# MM2_plates.net
KiCad netlist of a schematic drawn in EAGLE
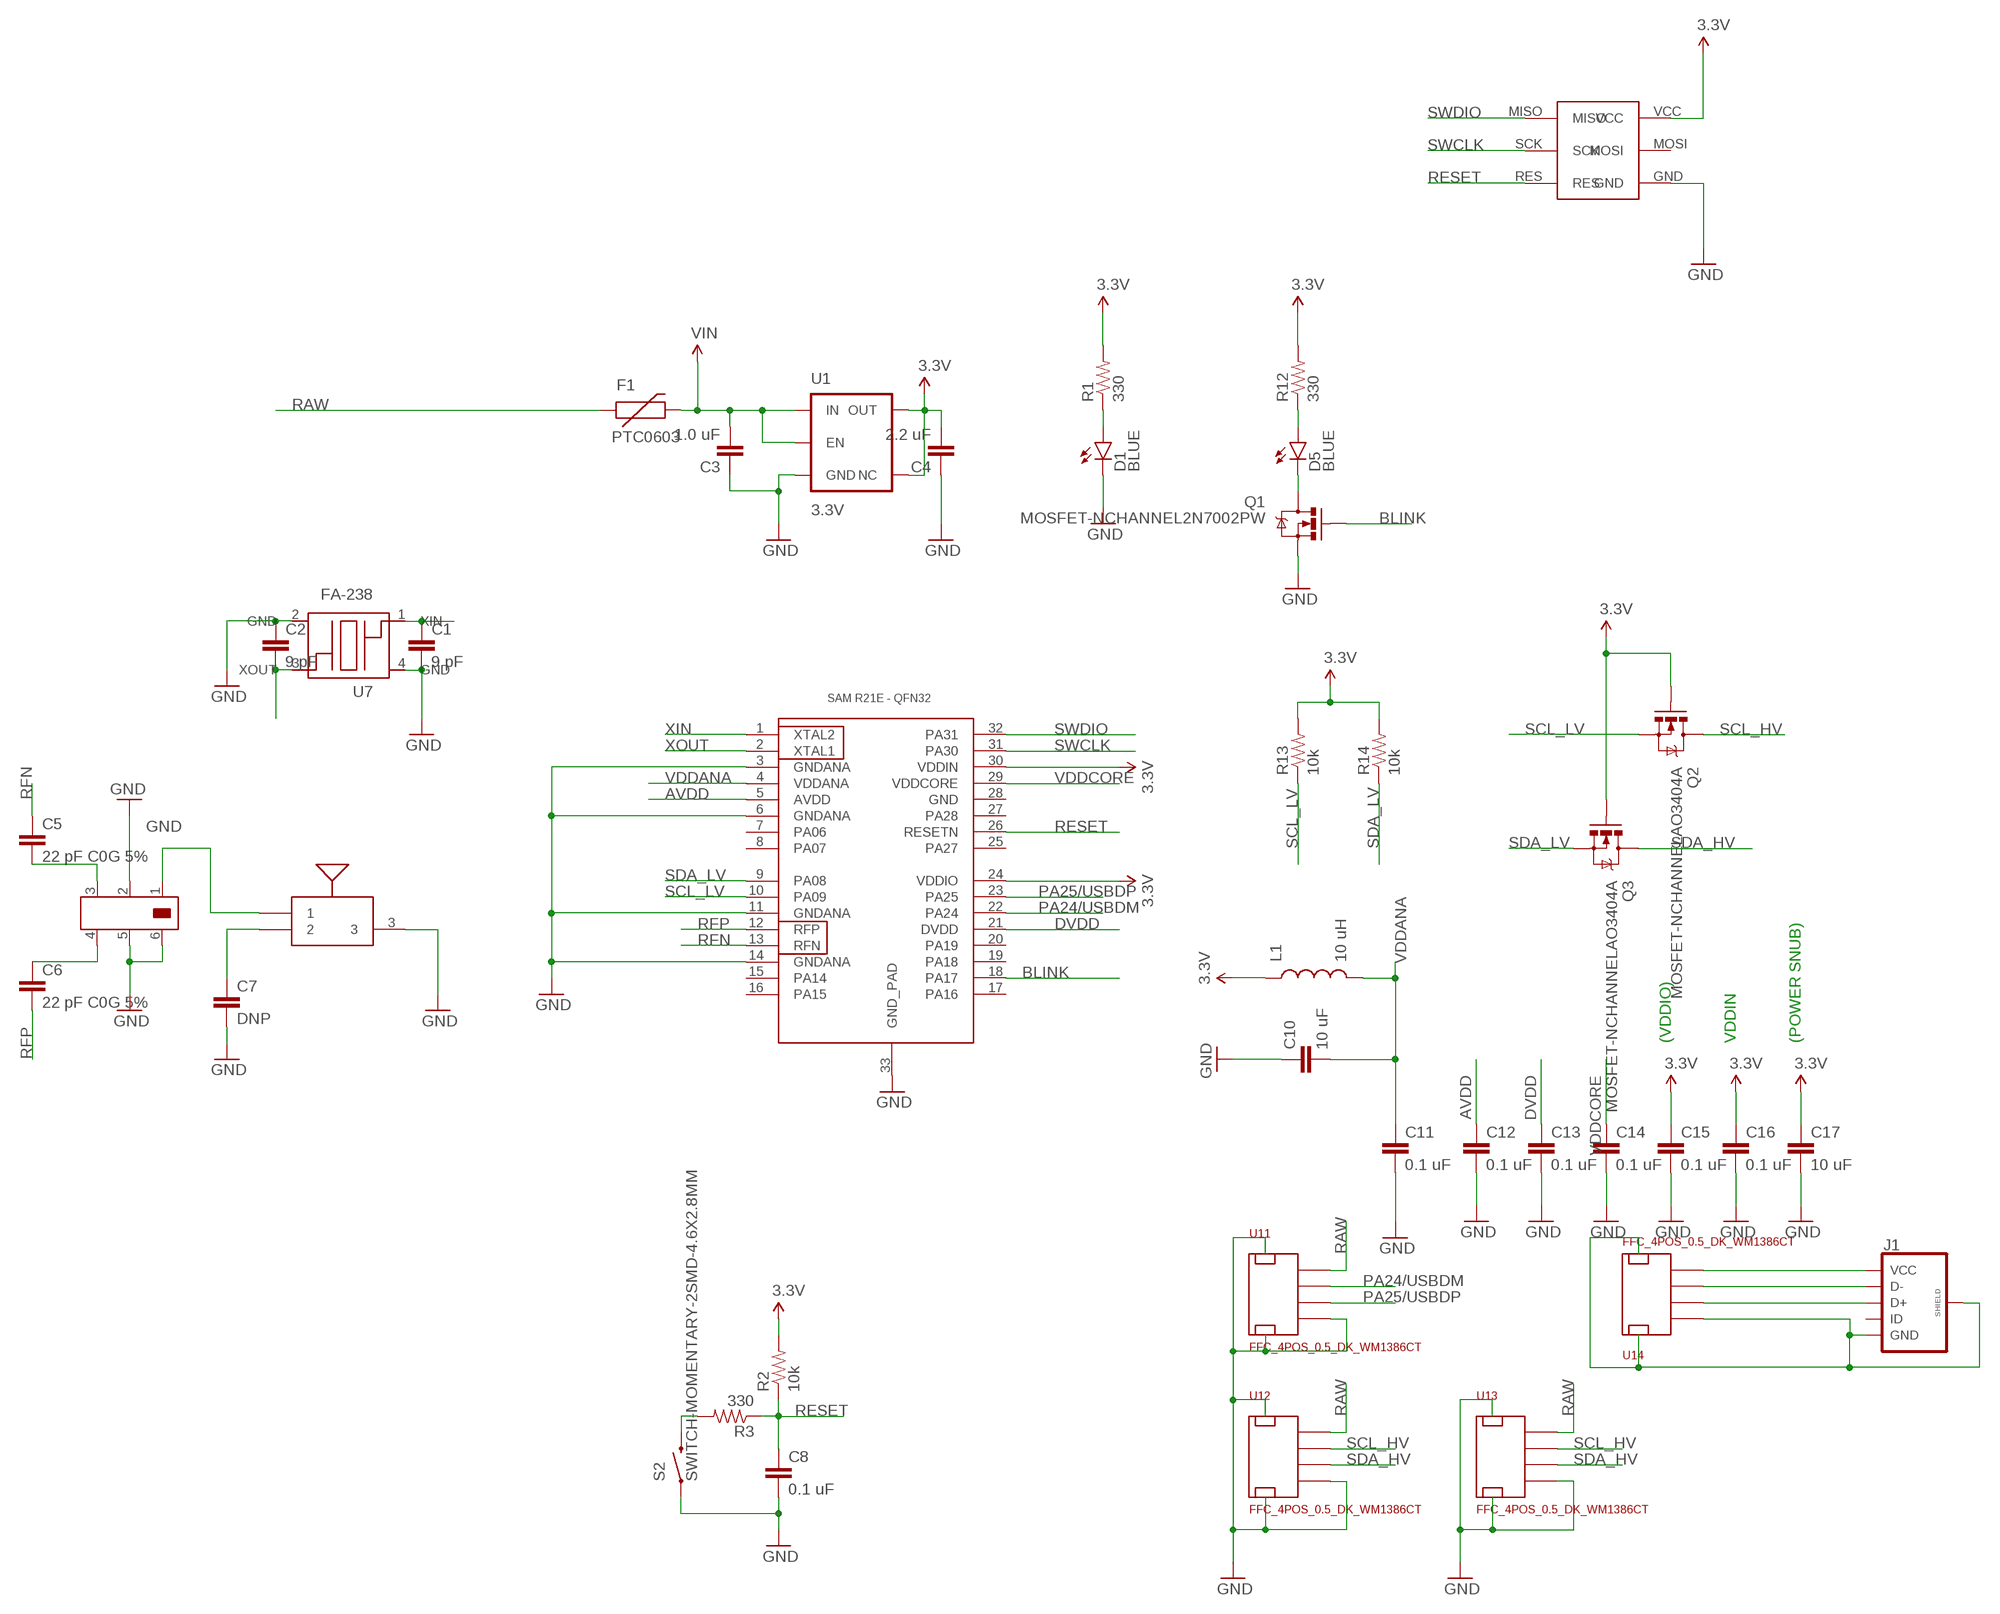
[diagram p0: schematic, sheet 1, part 1 of 2]
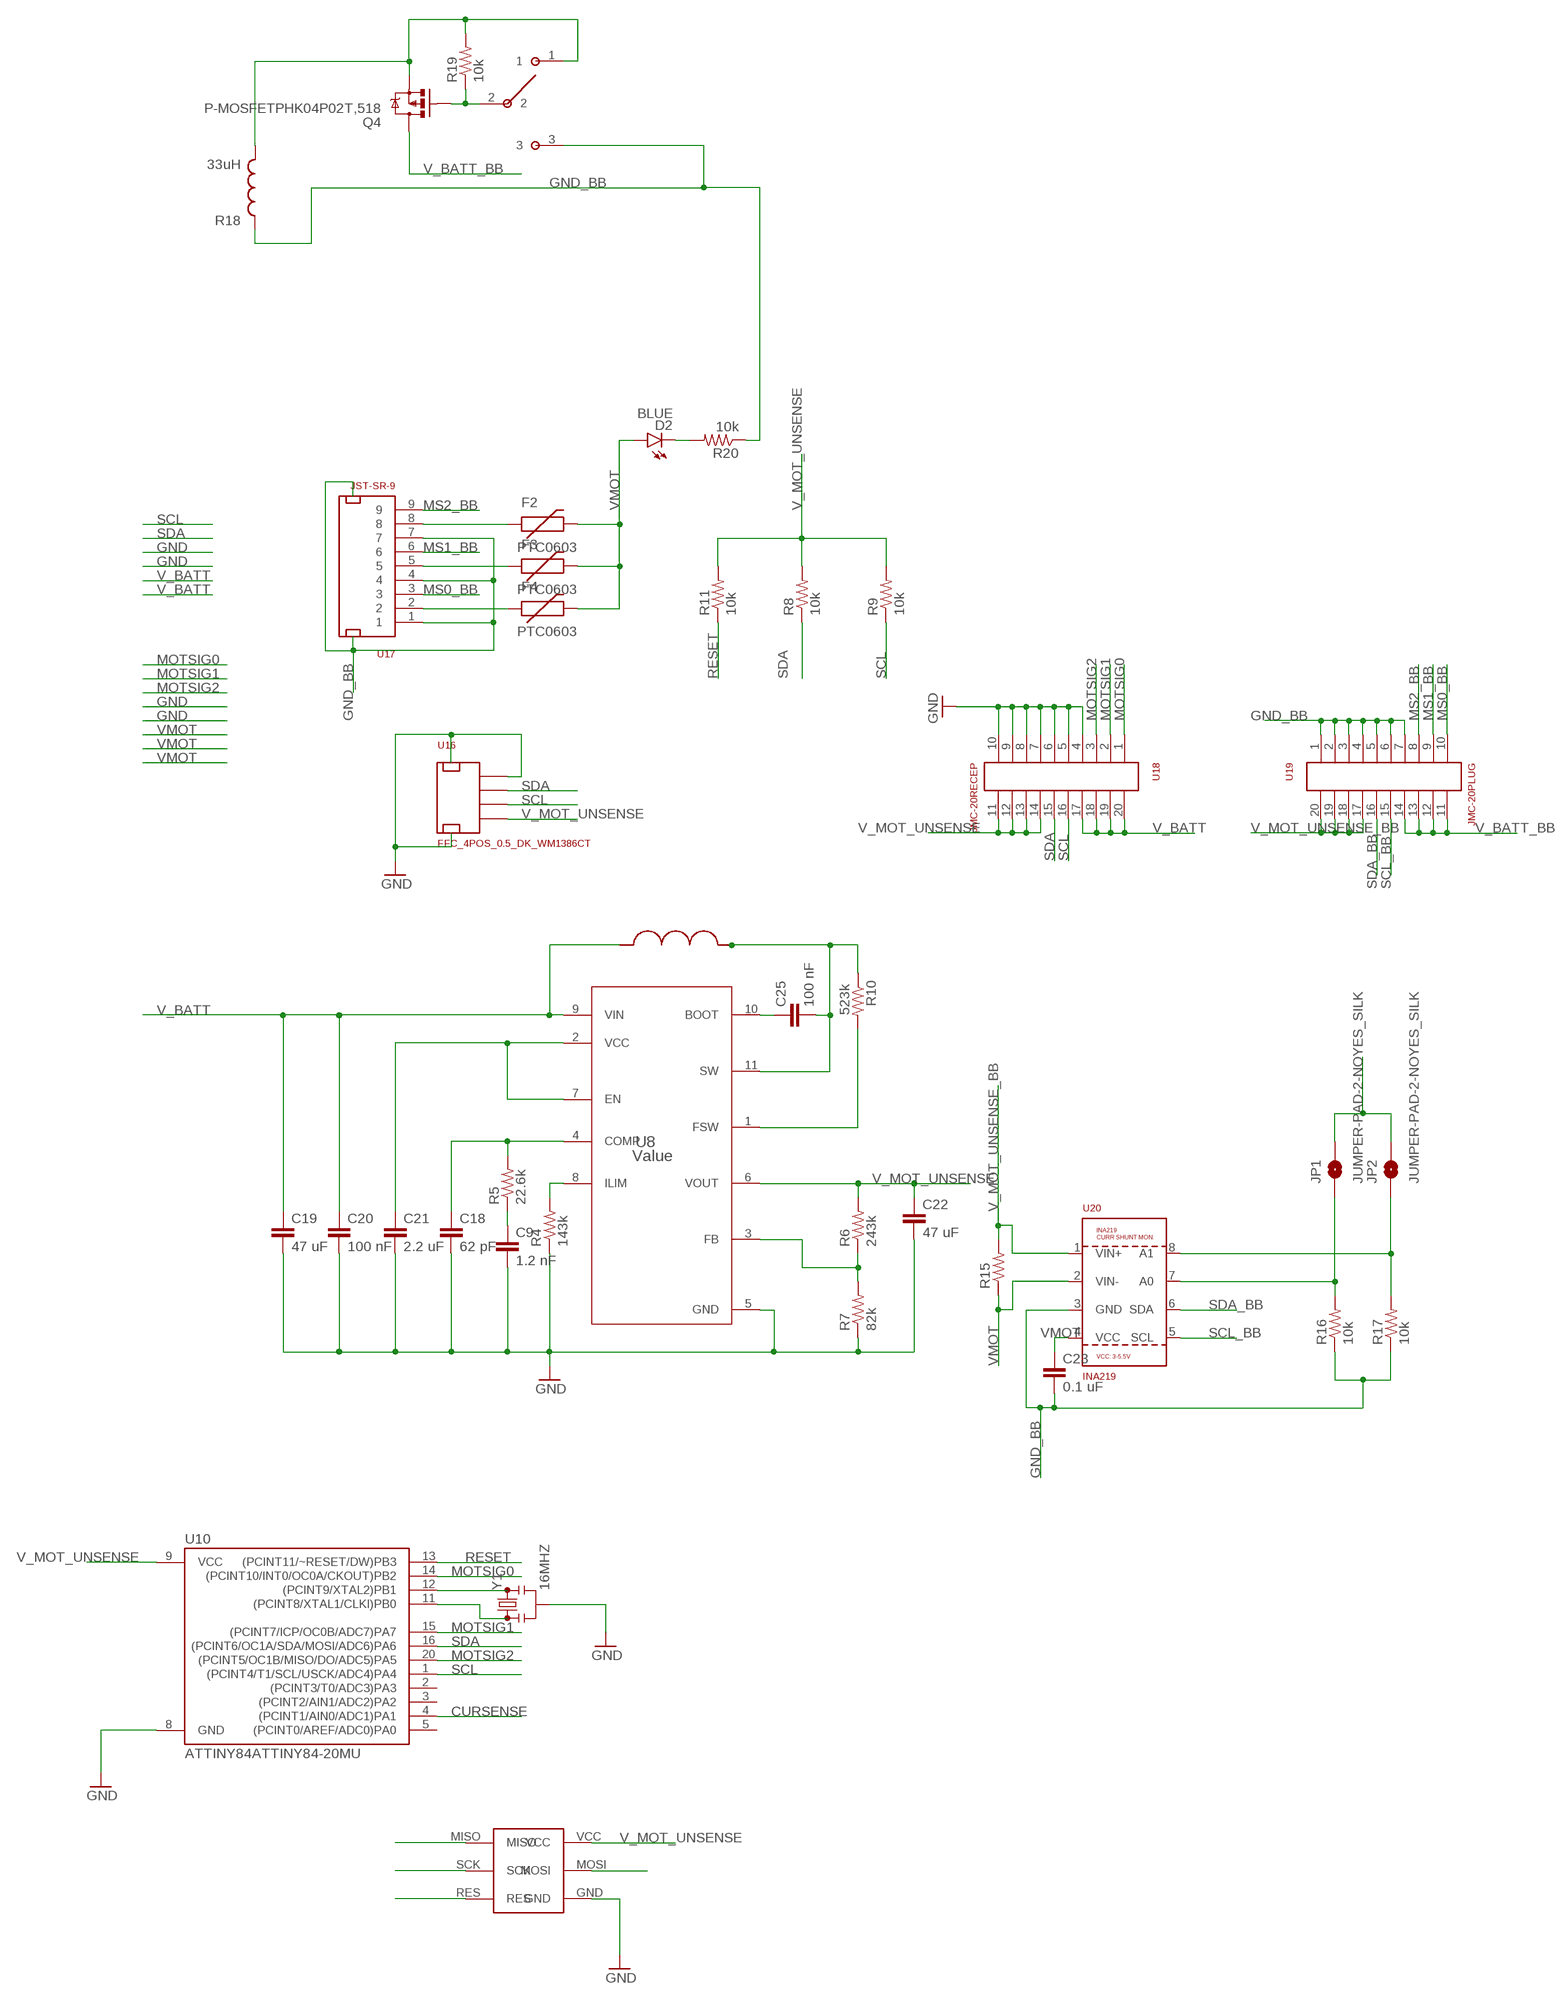
[diagram p1: schematic, sheet 1, part 2 of 2]

(export (version "E")
  (design (tool "Eeschema 10.0.6"))
  (components
    (comp (ref "C1")
      (value "9 pF")
      (footprint "eagle-import:0402-CAP")
      (libsource (lib "eagle-import") (part "CAP0402-CAP"))
    )
    (comp (ref "C2")
      (value "9 pF")
      (footprint "eagle-import:0402-CAP")
      (libsource (lib "eagle-import") (part "CAP0402-CAP"))
    )
    (comp (ref "C3")
      (value "1.0 uF")
      (footprint "eagle-import:0402-CAP")
      (libsource (lib "eagle-import") (part "CAP0402-CAP"))
    )
    (comp (ref "C4")
      (value "2.2 uF")
      (footprint "eagle-import:0402-CAP")
      (libsource (lib "eagle-import") (part "CAP0402-CAP"))
    )
    (comp (ref "C5")
      (value "22 pF C0G 5%")
      (footprint "eagle-import:0402-CAP")
      (libsource (lib "eagle-import") (part "CAP0402-CAP"))
    )
    (comp (ref "C6")
      (value "22 pF C0G 5%")
      (footprint "eagle-import:0402-CAP")
      (libsource (lib "eagle-import") (part "CAP0402-CAP"))
    )
    (comp (ref "C7")
      (value "DNP")
      (footprint "eagle-import:0402-CAP")
      (libsource (lib "eagle-import") (part "CAP0402-CAP"))
    )
    (comp (ref "C8")
      (value "0.1 uF")
      (footprint "eagle-import:0402-CAP")
      (libsource (lib "eagle-import") (part "CAP0402-CAP"))
    )
    (comp (ref "C9")
      (value "1.2 nF")
      (footprint "eagle-import:0805")
      (libsource (lib "eagle-import") (part "CAP0805"))
    )
    (comp (ref "C10")
      (value "10 uF")
      (footprint "eagle-import:0402-CAP")
      (libsource (lib "eagle-import") (part "CAP0402-CAP"))
    )
    (comp (ref "C11")
      (value "0.1 uF")
      (footprint "eagle-import:0402-CAP")
      (libsource (lib "eagle-import") (part "CAP0402-CAP"))
    )
    (comp (ref "C12")
      (value "0.1 uF")
      (footprint "eagle-import:0402-CAP")
      (libsource (lib "eagle-import") (part "CAP0402-CAP"))
    )
    (comp (ref "C13")
      (value "0.1 uF")
      (footprint "eagle-import:0402-CAP")
      (libsource (lib "eagle-import") (part "CAP0402-CAP"))
    )
    (comp (ref "C14")
      (value "0.1 uF")
      (footprint "eagle-import:0402-CAP")
      (libsource (lib "eagle-import") (part "CAP0402-CAP"))
    )
    (comp (ref "C15")
      (value "0.1 uF")
      (footprint "eagle-import:0402-CAP")
      (libsource (lib "eagle-import") (part "CAP0402-CAP"))
    )
    (comp (ref "C16")
      (value "0.1 uF")
      (footprint "eagle-import:0402-CAP")
      (libsource (lib "eagle-import") (part "CAP0402-CAP"))
    )
    (comp (ref "C17")
      (value "10 uF")
      (footprint "eagle-import:0402-CAP")
      (libsource (lib "eagle-import") (part "CAP0402-CAP"))
    )
    (comp (ref "C18")
      (value "62 pF")
      (footprint "eagle-import:0805")
      (libsource (lib "eagle-import") (part "CAP0805"))
    )
    (comp (ref "C19")
      (value "47 uF")
      (footprint "eagle-import:1206")
      (libsource (lib "eagle-import") (part "CAP1206"))
    )
    (comp (ref "C20")
      (value "100 nF")
      (footprint "eagle-import:0402-CAP")
      (libsource (lib "eagle-import") (part "CAP0402-CAP"))
    )
    (comp (ref "C21")
      (value "2.2 uF")
      (footprint "eagle-import:0603-CAP")
      (libsource (lib "eagle-import") (part "CAP0603-CAP"))
    )
    (comp (ref "C22")
      (value "47 uF")
      (footprint "eagle-import:1206")
      (libsource (lib "eagle-import") (part "CAP1206"))
    )
    (comp (ref "C23")
      (value "0.1 uF")
      (footprint "eagle-import:0402-CAP")
      (libsource (lib "eagle-import") (part "CAP0402-CAP"))
    )
    (comp (ref "C25")
      (value "100 nF")
      (footprint "eagle-import:0402-CAP")
      (libsource (lib "eagle-import") (part "CAP0402-CAP"))
    )
    (comp (ref "D1")
      (value "BLUE")
      (footprint "eagle-import:LED-0603")
      (libsource (lib "eagle-import") (part "LED-BLUE0603"))
    )
    (comp (ref "D2")
      (value "BLUE")
      (footprint "eagle-import:LED-0603")
      (libsource (lib "eagle-import") (part "LED-BLUE0603"))
    )
    (comp (ref "D5")
      (value "BLUE")
      (footprint "eagle-import:LED-0603")
      (libsource (lib "eagle-import") (part "LED-BLUE0603"))
    )
    (comp (ref "F1")
      (value "PTC0603")
      (footprint "eagle-import:0603")
      (libsource (lib "eagle-import") (part "PTC0603"))
    )
    (comp (ref "F2")
      (value "PTC0603")
      (footprint "eagle-import:0603")
      (libsource (lib "eagle-import") (part "PTC0603"))
    )
    (comp (ref "F3")
      (value "PTC0603")
      (footprint "eagle-import:0603")
      (libsource (lib "eagle-import") (part "PTC0603"))
    )
    (comp (ref "F4")
      (value "PTC0603")
      (footprint "eagle-import:0603")
      (libsource (lib "eagle-import") (part "PTC0603"))
    )
    (comp (ref "J1")
      (value "USB_MICROB_PLUGCONN-11752")
      (footprint "eagle-import:USB-B-MICRO-SMD_V03")
      (libsource (lib "eagle-import") (part "USB_MICROB_PLUGCONN-11752"))
    )
    (comp (ref "JP1")
      (value "JUMPER-PAD-2-NOYES_SILK")
      (footprint "eagle-import:PAD-JUMPER-2-NO_YES_SILK")
      (libsource (lib "eagle-import") (part "JUMPER-PAD-2-NOYES_SILK"))
    )
    (comp (ref "JP2")
      (value "JUMPER-PAD-2-NOYES_SILK")
      (footprint "eagle-import:PAD-JUMPER-2-NO_YES_SILK")
      (libsource (lib "eagle-import") (part "JUMPER-PAD-2-NOYES_SILK"))
    )
    (comp (ref "L1")
      (value "10 uH")
      (footprint "eagle-import:0603")
      (libsource (lib "eagle-import") (part "INDUCTOR0603"))
    )
    (comp (ref "L2")
      (value "WE_IND_4.1MM732-8229-1-ND")
      (footprint "eagle-import:WE_4MM_IND")
      (libsource (lib "eagle-import") (part "WE_IND_4.1MM732-8229-1-ND"))
    )
    (comp (ref "Q1")
      (value "MOSFET-NCHANNEL2N7002PW")
      (footprint "eagle-import:SOT323")
      (libsource (lib "eagle-import") (part "MOSFET-NCHANNEL2N7002PW"))
    )
    (comp (ref "Q2")
      (value "MOSFET-NCHANNELAO3404A")
      (footprint "eagle-import:SOT23-3")
      (libsource (lib "eagle-import") (part "MOSFET-NCHANNELAO3404A"))
    )
    (comp (ref "Q3")
      (value "MOSFET-NCHANNELAO3404A")
      (footprint "eagle-import:SOT23-3")
      (libsource (lib "eagle-import") (part "MOSFET-NCHANNELAO3404A"))
    )
    (comp (ref "Q4")
      (value "P-MOSFETPHK04P02T,518")
      (footprint "eagle-import:SO08")
      (libsource (lib "eagle-import") (part "P-MOSFETPHK04P02T,518"))
    )
    (comp (ref "R1")
      (value "330")
      (footprint "eagle-import:0402-RES")
      (libsource (lib "eagle-import") (part "RESISTOR0402-RES"))
    )
    (comp (ref "R2")
      (value "10k")
      (footprint "eagle-import:0402-RES")
      (libsource (lib "eagle-import") (part "RESISTOR0402-RES"))
    )
    (comp (ref "R3")
      (value "330")
      (footprint "eagle-import:0402-RES")
      (libsource (lib "eagle-import") (part "RESISTOR0402-RES"))
    )
    (comp (ref "R4")
      (value "143k")
      (footprint "eagle-import:1206")
      (libsource (lib "eagle-import") (part "SparkFun-Resistors_RESISTOR1206"))
    )
    (comp (ref "R5")
      (value "22.6k")
      (footprint "eagle-import:0402-RES")
      (libsource (lib "eagle-import") (part "RESISTOR0402-RES"))
    )
    (comp (ref "R6")
      (value "243k")
      (footprint "eagle-import:0402-RES")
      (libsource (lib "eagle-import") (part "RESISTOR0402-RES"))
    )
    (comp (ref "R7")
      (value "82k")
      (footprint "eagle-import:0603-RES")
      (libsource (lib "eagle-import") (part "RESISTOR0603-RES"))
    )
    (comp (ref "R8")
      (value "10k")
      (footprint "eagle-import:0402-RES")
      (libsource (lib "eagle-import") (part "RESISTOR0402-RES"))
    )
    (comp (ref "R9")
      (value "10k")
      (footprint "eagle-import:0402-RES")
      (libsource (lib "eagle-import") (part "RESISTOR0402-RES"))
    )
    (comp (ref "R10")
      (value "523k")
      (footprint "eagle-import:1206")
      (libsource (lib "eagle-import") (part "SparkFun-Resistors_RESISTOR1206"))
    )
    (comp (ref "R11")
      (value "10k")
      (footprint "eagle-import:0402-RES")
      (libsource (lib "eagle-import") (part "RESISTOR0402-RES"))
    )
    (comp (ref "R12")
      (value "330")
      (footprint "eagle-import:0402-RES")
      (libsource (lib "eagle-import") (part "RESISTOR0402-RES"))
    )
    (comp (ref "R13")
      (value "10k")
      (footprint "eagle-import:0402-RES")
      (libsource (lib "eagle-import") (part "RESISTOR0402-RES"))
    )
    (comp (ref "R14")
      (value "10k")
      (footprint "eagle-import:0402-RES")
      (libsource (lib "eagle-import") (part "RESISTOR0402-RES"))
    )
    (comp (ref "R15")
      (value "RESISTOR0402-RES")
      (footprint "eagle-import:0402-RES")
      (libsource (lib "eagle-import") (part "RESISTOR0402-RES"))
    )
    (comp (ref "R16")
      (value "10k")
      (footprint "eagle-import:0402-RES")
      (libsource (lib "eagle-import") (part "RESISTOR0402-RES"))
    )
    (comp (ref "R17")
      (value "10k")
      (footprint "eagle-import:0402-RES")
      (libsource (lib "eagle-import") (part "RESISTOR0402-RES"))
    )
    (comp (ref "R18")
      (value "33uH")
      (footprint "eagle-import:INDUCTOR-1206")
      (libsource (lib "eagle-import") (part "INDUCTORH1206"))
    )
    (comp (ref "R19")
      (value "10k")
      (footprint "eagle-import:0402-RES")
      (libsource (lib "eagle-import") (part "RESISTOR0402-RES"))
    )
    (comp (ref "R20")
      (value "10k")
      (footprint "eagle-import:0402-RES")
      (libsource (lib "eagle-import") (part "RESISTOR0402-RES"))
    )
    (comp (ref "S1")
      (value "AYZ0102AGRLC")
      (footprint "eagle-import:AYZ0102AGRLC")
      (libsource (lib "eagle-import") (part "AYZ0102AGRLC"))
    )
    (comp (ref "S2")
      (value "SWITCH-MOMENTARY-2SMD-4.6X2.8MM")
      (footprint "eagle-import:TACTILE_SWITCH_SMD_4.6X2.8MM")
      (libsource (lib "eagle-import") (part "SWITCH-MOMENTARY-2SMD-4.6X2.8MM"))
    )
    (comp (ref "U1")
      (value "3.3V")
      (footprint "eagle-import:SOT23-5")
      (libsource (lib "eagle-import") (part "V_REG_AP2112K-3.3V"))
    )
    (comp (ref "U2")
      (value "ATSAMR21E18A-MUT")
      (footprint "eagle-import:QFN32")
      (libsource (lib "eagle-import") (part "ATSAMR21E18A-MUT"))
    )
    (comp (ref "U5")
      (value "PULSE_ANT_2.4GHZ")
      (footprint "eagle-import:ANT_BAR")
      (libsource (lib "eagle-import") (part "PULSE_ANT_2.4GHZ"))
    )
    (comp (ref "U6")
      (value "JOHANSON_2450BM15A0015E")
      (footprint "eagle-import:0805_BALUN")
      (libsource (lib "eagle-import") (part "JOHANSON_2450BM15A0015E"))
    )
    (comp (ref "U7")
      (value "FA-238")
      (footprint "eagle-import:FA-238")
      (libsource (lib "eagle-import") (part "FA-238"))
    )
    (comp (ref "U8")
      (value "Value")
      (footprint "eagle-import:RNR0011A")
      (fields
        (field (name "MANUFACTURER") "Texas Instruments")
        (field (name "MANUFACTURER_PART_NUMBER") "TPS61089RNRR")
      )
      (libsource (lib "eagle-import") (part "TPS61089RNRR"))
    )
    (comp (ref "U9")
      (value "TC2030_ISP")
      (footprint "eagle-import:TAG_CONNECT_6PIN_NOSIDEHOLES")
      (libsource (lib "eagle-import") (part "TC2030_ISP"))
    )
    (comp (ref "U10")
      (value "ATTINY84ATTINY84-20MU")
      (footprint "eagle-import:QFN20")
      (libsource (lib "eagle-import") (part "ATTINY84ATTINY84-20MU"))
    )
    (comp (ref "U11")
      (value "FFC_4POS_0.5_DK_WM1386CT")
      (footprint "eagle-import:503480")
      (libsource (lib "eagle-import") (part "FFC_4POS_0.5_DK_WM1386CT"))
    )
    (comp (ref "U12")
      (value "FFC_4POS_0.5_DK_WM1386CT")
      (footprint "eagle-import:503480")
      (libsource (lib "eagle-import") (part "FFC_4POS_0.5_DK_WM1386CT"))
    )
    (comp (ref "U13")
      (value "FFC_4POS_0.5_DK_WM1386CT")
      (footprint "eagle-import:503480")
      (libsource (lib "eagle-import") (part "FFC_4POS_0.5_DK_WM1386CT"))
    )
    (comp (ref "U14")
      (value "FFC_4POS_0.5_DK_WM1386CT")
      (footprint "eagle-import:503480")
      (libsource (lib "eagle-import") (part "FFC_4POS_0.5_DK_WM1386CT"))
    )
    (comp (ref "U16")
      (value "FFC_4POS_0.5_DK_WM1386CT")
      (footprint "eagle-import:503480")
      (libsource (lib "eagle-import") (part "FFC_4POS_0.5_DK_WM1386CT"))
    )
    (comp (ref "U17")
      (value "JST-SR-9")
      (footprint "eagle-import:JST-SR-9")
      (libsource (lib "eagle-import") (part "JST-SR-9"))
    )
    (comp (ref "U18")
      (value "JMC-20RECEP")
      (footprint "eagle-import:JST_RECEP_JMC0.5_20")
      (libsource (lib "eagle-import") (part "JMC-20RECEP"))
    )
    (comp (ref "U19")
      (value "JMC-20PLUG")
      (footprint "eagle-import:JST_PLUG_JMC0.5_20")
      (libsource (lib "eagle-import") (part "JMC-20PLUG"))
    )
    (comp (ref "U20")
      (value "INA219")
      (footprint "eagle-import:SOT-23-8")
      (libsource (lib "eagle-import") (part "INA219"))
    )
    (comp (ref "U21")
      (value "TC2030_ISP")
      (footprint "eagle-import:TAG_CONNECT_6PIN_NOSIDEHOLES")
      (libsource (lib "eagle-import") (part "TC2030_ISP"))
    )
    (comp (ref "Y1")
      (value "16MHZ")
      (footprint "eagle-import:RESONATOR-SMD")
      (libsource (lib "eagle-import") (part "RESONATOR16MHZ"))
    )
  )
  (nets
    (net (code "1") (name "/AVDD") (class "Default")
      (node (ref "C12") (pin "1") (pinfunction "1_1") (pintype "passive"))
      (node (ref "U2") (pin "5") (pinfunction "AVDD_5") (pintype "bidirectional"))
    )
    (net (code "2") (name "/BLINK") (class "Default")
      (node (ref "Q1") (pin "1") (pinfunction "G_1") (pintype "passive"))
      (node (ref "U2") (pin "18") (pinfunction "PA17_18") (pintype "bidirectional"))
    )
    (net (code "3") (name "/CURSENSE") (class "Default")
      (node (ref "U10") (pin "4") (pinfunction "(PCINT1/AIN0/ADC1)PA1_4") (pintype "bidirectional"))
    )
    (net (code "4") (name "/DVDD") (class "Default")
      (node (ref "C13") (pin "1") (pinfunction "1_1") (pintype "passive"))
      (node (ref "U2") (pin "21") (pinfunction "DVDD_21") (pintype "bidirectional"))
    )
    (net (code "5") (name "/GND_BB") (class "Default")
      (node (ref "C23") (pin "2") (pinfunction "2_2") (pintype "passive"))
      (node (ref "R16") (pin "1") (pinfunction "1_1") (pintype "passive"))
      (node (ref "R17") (pin "1") (pinfunction "1_1") (pintype "passive"))
      (node (ref "R18") (pin "P$1") (pinfunction "1_P$1") (pintype "passive"))
      (node (ref "R20") (pin "1") (pinfunction "1_1") (pintype "passive"))
      (node (ref "S1") (pin "3") (pinfunction "3_3") (pintype "bidirectional"))
      (node (ref "U17") (pin "1") (pinfunction "1_1") (pintype "bidirectional"))
      (node (ref "U17") (pin "4") (pinfunction "4_4") (pintype "bidirectional"))
      (node (ref "U17") (pin "7") (pinfunction "7_7") (pintype "bidirectional"))
      (node (ref "U17") (pin "P$10") (pinfunction "P$1_P$10") (pintype "bidirectional"))
      (node (ref "U17") (pin "P$11") (pinfunction "P$2_P$11") (pintype "bidirectional"))
      (node (ref "U19") (pin "1") (pinfunction "P$1_1") (pintype "bidirectional"))
      (node (ref "U19") (pin "2") (pinfunction "P$2_2") (pintype "bidirectional"))
      (node (ref "U19") (pin "3") (pinfunction "P$3_3") (pintype "bidirectional"))
      (node (ref "U19") (pin "4") (pinfunction "P$4_4") (pintype "bidirectional"))
      (node (ref "U19") (pin "5") (pinfunction "P$5_5") (pintype "bidirectional"))
      (node (ref "U19") (pin "6") (pinfunction "P$6_6") (pintype "bidirectional"))
      (node (ref "U19") (pin "7") (pinfunction "P$7_7") (pintype "bidirectional"))
      (node (ref "U20") (pin "3") (pinfunction "GND_3") (pintype "bidirectional"))
    )
    (net (code "6") (name "/MOTSIG0") (class "Default")
      (node (ref "U10") (pin "14") (pinfunction "(PCINT10/INT0/OC0A/CKOUT)PB2_14") (pintype "bidirectional"))
      (node (ref "U18") (pin "1") (pinfunction "P$1_1") (pintype "bidirectional"))
    )
    (net (code "7") (name "/MOTSIG1") (class "Default")
      (node (ref "U10") (pin "15") (pinfunction "(PCINT7/ICP/OC0B/ADC7)PA7_15") (pintype "bidirectional"))
      (node (ref "U18") (pin "2") (pinfunction "P$2_2") (pintype "bidirectional"))
    )
    (net (code "8") (name "/MOTSIG2") (class "Default")
      (node (ref "U10") (pin "20") (pinfunction "(PCINT5/OC1B/MISO/DO/ADC5)PA5_20") (pintype "bidirectional"))
      (node (ref "U18") (pin "3") (pinfunction "P$3_3") (pintype "bidirectional"))
      (node (ref "U21") (pin "MISO") (pinfunction "MISO_MISO") (pintype "bidirectional"))
    )
    (net (code "9") (name "/MS0_BB") (class "Default")
      (node (ref "U17") (pin "3") (pinfunction "3_3") (pintype "bidirectional"))
      (node (ref "U19") (pin "10") (pinfunction "P$10_10") (pintype "bidirectional"))
    )
    (net (code "10") (name "/MS1_BB") (class "Default")
      (node (ref "U17") (pin "6") (pinfunction "6_6") (pintype "bidirectional"))
      (node (ref "U19") (pin "9") (pinfunction "P$9_9") (pintype "bidirectional"))
    )
    (net (code "11") (name "/MS2_BB") (class "Default")
      (node (ref "U17") (pin "9") (pinfunction "9_9") (pintype "bidirectional"))
      (node (ref "U19") (pin "8") (pinfunction "P$8_8") (pintype "bidirectional"))
    )
    (net (code "12") (name "/PA24{slash}USBDM") (class "Default")
      (node (ref "U11") (pin "P$2") (pinfunction "P$3_P$2") (pintype "bidirectional"))
      (node (ref "U2") (pin "22") (pinfunction "PA24_22") (pintype "bidirectional"))
    )
    (net (code "13") (name "/PA25{slash}USBDP") (class "Default")
      (node (ref "U11") (pin "P$3") (pinfunction "P$2_P$3") (pintype "bidirectional"))
      (node (ref "U2") (pin "23") (pinfunction "PA25_23") (pintype "bidirectional"))
    )
    (net (code "14") (name "/RAW") (class "Default")
      (node (ref "F1") (pin "1") (pinfunction "1_1") (pintype "bidirectional"))
      (node (ref "U11") (pin "P$1") (pinfunction "P$4_P$1") (pintype "bidirectional"))
      (node (ref "U12") (pin "P$1") (pinfunction "P$4_P$1") (pintype "bidirectional"))
      (node (ref "U13") (pin "P$1") (pinfunction "P$4_P$1") (pintype "bidirectional"))
    )
    (net (code "15") (name "/RESET") (class "Default")
      (node (ref "C8") (pin "1") (pinfunction "1_1") (pintype "passive"))
      (node (ref "R11") (pin "1") (pinfunction "1_1") (pintype "passive"))
      (node (ref "R2") (pin "1") (pinfunction "1_1") (pintype "passive"))
      (node (ref "R3") (pin "1") (pinfunction "1_1") (pintype "passive"))
      (node (ref "U10") (pin "13") (pinfunction "(PCINT11/~{RESET/DW})PB3_13") (pintype "bidirectional"))
      (node (ref "U2") (pin "26") (pinfunction "RESETN_26") (pintype "bidirectional"))
      (node (ref "U21") (pin "RES") (pinfunction "RES_RES") (pintype "bidirectional"))
      (node (ref "U9") (pin "RES") (pinfunction "RES_RES") (pintype "bidirectional"))
    )
    (net (code "16") (name "/RFN") (class "Default")
      (node (ref "C5") (pin "1") (pinfunction "1_1") (pintype "passive"))
      (node (ref "U2") (pin "13") (pinfunction "RFN_13") (pintype "bidirectional"))
    )
    (net (code "17") (name "/RFP") (class "Default")
      (node (ref "C6") (pin "2") (pinfunction "2_2") (pintype "passive"))
      (node (ref "U2") (pin "12") (pinfunction "RFP_12") (pintype "bidirectional"))
    )
    (net (code "18") (name "/SCL") (class "Default")
      (node (ref "R9") (pin "1") (pinfunction "1_1") (pintype "passive"))
      (node (ref "U10") (pin "1") (pinfunction "(PCINT4/T1/SCL/USCK/ADC4)PA4_1") (pintype "bidirectional"))
      (node (ref "U16") (pin "P$3") (pinfunction "P$2_P$3") (pintype "bidirectional"))
      (node (ref "U18") (pin "16") (pinfunction "P$16_16") (pintype "bidirectional"))
      (node (ref "U21") (pin "SCK") (pinfunction "SCK_SCK") (pintype "bidirectional"))
    )
    (net (code "19") (name "/SCL_BB") (class "Default")
      (node (ref "U19") (pin "15") (pinfunction "P$15_15") (pintype "bidirectional"))
      (node (ref "U20") (pin "5") (pinfunction "SCL_5") (pintype "bidirectional"))
    )
    (net (code "20") (name "/SCL_HV") (class "Default")
      (node (ref "Q2") (pin "3") (pinfunction "D_3") (pintype "passive"))
      (node (ref "U12") (pin "P$2") (pinfunction "P$3_P$2") (pintype "bidirectional"))
      (node (ref "U13") (pin "P$2") (pinfunction "P$3_P$2") (pintype "bidirectional"))
    )
    (net (code "21") (name "/SCL_LV") (class "Default")
      (node (ref "Q2") (pin "2") (pinfunction "S_2") (pintype "passive"))
      (node (ref "R13") (pin "1") (pinfunction "1_1") (pintype "passive"))
      (node (ref "U2") (pin "10") (pinfunction "PA09_10") (pintype "bidirectional"))
    )
    (net (code "22") (name "/SDA") (class "Default")
      (node (ref "R8") (pin "1") (pinfunction "1_1") (pintype "passive"))
      (node (ref "U10") (pin "16") (pinfunction "(PCINT6/OC1A/SDA/MOSI/ADC6)PA6_16") (pintype "bidirectional"))
      (node (ref "U16") (pin "P$2") (pinfunction "P$3_P$2") (pintype "bidirectional"))
      (node (ref "U18") (pin "15") (pinfunction "P$15_15") (pintype "bidirectional"))
      (node (ref "U21") (pin "MOSI") (pinfunction "MOSI_MOSI") (pintype "bidirectional"))
    )
    (net (code "23") (name "/SDA_BB") (class "Default")
      (node (ref "U19") (pin "16") (pinfunction "P$16_16") (pintype "bidirectional"))
      (node (ref "U20") (pin "6") (pinfunction "SDA_6") (pintype "bidirectional"))
    )
    (net (code "24") (name "/SDA_HV") (class "Default")
      (node (ref "Q3") (pin "3") (pinfunction "D_3") (pintype "passive"))
      (node (ref "U12") (pin "P$3") (pinfunction "P$2_P$3") (pintype "bidirectional"))
      (node (ref "U13") (pin "P$3") (pinfunction "P$2_P$3") (pintype "bidirectional"))
    )
    (net (code "25") (name "/SDA_LV") (class "Default")
      (node (ref "Q3") (pin "2") (pinfunction "S_2") (pintype "passive"))
      (node (ref "R14") (pin "1") (pinfunction "1_1") (pintype "passive"))
      (node (ref "U2") (pin "9") (pinfunction "PA08_9") (pintype "bidirectional"))
    )
    (net (code "26") (name "/SWCLK") (class "Default")
      (node (ref "U2") (pin "31") (pinfunction "PA30_31") (pintype "bidirectional"))
      (node (ref "U9") (pin "SCK") (pinfunction "SCK_SCK") (pintype "bidirectional"))
    )
    (net (code "27") (name "/SWDIO") (class "Default")
      (node (ref "U2") (pin "32") (pinfunction "PA31_32") (pintype "bidirectional"))
      (node (ref "U9") (pin "MISO") (pinfunction "MISO_MISO") (pintype "bidirectional"))
    )
    (net (code "28") (name "/VDDANA") (class "Default")
      (node (ref "C10") (pin "2") (pinfunction "2_2") (pintype "passive"))
      (node (ref "C11") (pin "1") (pinfunction "1_1") (pintype "passive"))
      (node (ref "L1") (pin "2") (pinfunction "2_2") (pintype "passive"))
      (node (ref "U2") (pin "4") (pinfunction "VDDANA_4") (pintype "bidirectional"))
    )
    (net (code "29") (name "/VDDCORE") (class "Default")
      (node (ref "C14") (pin "1") (pinfunction "1_1") (pintype "passive"))
      (node (ref "U2") (pin "29") (pinfunction "VDDCORE_29") (pintype "bidirectional"))
    )
    (net (code "30") (name "/VMOT") (class "Default")
      (node (ref "C23") (pin "1") (pinfunction "1_1") (pintype "passive"))
      (node (ref "D2") (pin "A") (pinfunction "A_A") (pintype "passive"))
      (node (ref "F2") (pin "2") (pinfunction "2_2") (pintype "bidirectional"))
      (node (ref "F3") (pin "2") (pinfunction "2_2") (pintype "bidirectional"))
      (node (ref "F4") (pin "2") (pinfunction "2_2") (pintype "bidirectional"))
      (node (ref "JP1") (pin "2") (pinfunction "2_2") (pintype "passive"))
      (node (ref "JP2") (pin "2") (pinfunction "2_2") (pintype "passive"))
      (node (ref "R15") (pin "1") (pinfunction "1_1") (pintype "passive"))
      (node (ref "U20") (pin "2") (pinfunction "VIN-_2") (pintype "bidirectional"))
      (node (ref "U20") (pin "4") (pinfunction "VCC_4") (pintype "bidirectional"))
    )
    (net (code "31") (name "/V_BATT") (class "Default")
      (node (ref "C19") (pin "1") (pinfunction "1_1") (pintype "passive"))
      (node (ref "C20") (pin "1") (pinfunction "1_1") (pintype "passive"))
      (node (ref "L2") (pin "P$1") (pinfunction "P$1_P$1") (pintype "bidirectional"))
      (node (ref "U18") (pin "17") (pinfunction "P$17_17") (pintype "bidirectional"))
      (node (ref "U18") (pin "18") (pinfunction "P$18_18") (pintype "bidirectional"))
      (node (ref "U18") (pin "19") (pinfunction "P$19_19") (pintype "bidirectional"))
      (node (ref "U18") (pin "20") (pinfunction "P$20_20") (pintype "bidirectional"))
      (node (ref "U8") (pin "9") (pinfunction "VIN_9") (pintype "power_in"))
    )
    (net (code "32") (name "/V_BATT_BB") (class "Default")
      (node (ref "Q4") (pin "5") (pinfunction "D_5") (pintype "passive"))
      (node (ref "Q4") (pin "6") (pinfunction "D_6") (pintype "passive"))
      (node (ref "Q4") (pin "7") (pinfunction "D_7") (pintype "passive"))
      (node (ref "Q4") (pin "8") (pinfunction "D_8") (pintype "passive"))
      (node (ref "U19") (pin "11") (pinfunction "P$11_11") (pintype "bidirectional"))
      (node (ref "U19") (pin "12") (pinfunction "P$12_12") (pintype "bidirectional"))
      (node (ref "U19") (pin "13") (pinfunction "P$13_13") (pintype "bidirectional"))
      (node (ref "U19") (pin "14") (pinfunction "P$14_14") (pintype "bidirectional"))
    )
    (net (code "33") (name "/V_MOT_UNSENSE") (class "Default")
      (node (ref "C22") (pin "1") (pinfunction "1_1") (pintype "passive"))
      (node (ref "R11") (pin "2") (pinfunction "2_2") (pintype "passive"))
      (node (ref "R6") (pin "2") (pinfunction "2_2") (pintype "passive"))
      (node (ref "R8") (pin "2") (pinfunction "2_2") (pintype "passive"))
      (node (ref "R9") (pin "2") (pinfunction "2_2") (pintype "passive"))
      (node (ref "U10") (pin "9") (pinfunction "VCC_9") (pintype "bidirectional"))
      (node (ref "U16") (pin "P$4") (pinfunction "P$1_P$4") (pintype "bidirectional"))
      (node (ref "U18") (pin "11") (pinfunction "P$11_11") (pintype "bidirectional"))
      (node (ref "U18") (pin "12") (pinfunction "P$12_12") (pintype "bidirectional"))
      (node (ref "U18") (pin "13") (pinfunction "P$13_13") (pintype "bidirectional"))
      (node (ref "U18") (pin "14") (pinfunction "P$14_14") (pintype "bidirectional"))
      (node (ref "U21") (pin "VCC") (pinfunction "VCC_VCC") (pintype "bidirectional"))
      (node (ref "U8") (pin "6") (pinfunction "VOUT_6") (pintype "power_in"))
    )
    (net (code "34") (name "/V_MOT_UNSENSE_BB") (class "Default")
      (node (ref "R15") (pin "2") (pinfunction "2_2") (pintype "passive"))
      (node (ref "U19") (pin "17") (pinfunction "P$17_17") (pintype "bidirectional"))
      (node (ref "U19") (pin "18") (pinfunction "P$18_18") (pintype "bidirectional"))
      (node (ref "U19") (pin "19") (pinfunction "P$19_19") (pintype "bidirectional"))
      (node (ref "U19") (pin "20") (pinfunction "P$20_20") (pintype "bidirectional"))
      (node (ref "U20") (pin "1") (pinfunction "VIN+_1") (pintype "bidirectional"))
    )
    (net (code "35") (name "/XIN") (class "Default")
      (node (ref "C1") (pin "1") (pinfunction "1_1") (pintype "passive"))
      (node (ref "U2") (pin "1") (pinfunction "XTAL2_1") (pintype "bidirectional"))
      (node (ref "U7") (pin "1") (pinfunction "XIN_1") (pintype "bidirectional"))
    )
    (net (code "36") (name "/XOUT") (class "Default")
      (node (ref "C2") (pin "2") (pinfunction "2_2") (pintype "passive"))
      (node (ref "U2") (pin "2") (pinfunction "XTAL1_2") (pintype "bidirectional"))
      (node (ref "U7") (pin "3") (pinfunction "XOUT_3") (pintype "bidirectional"))
    )
    (net (code "37") (name "3.3V") (class "Default")
      (node (ref "C15") (pin "1") (pinfunction "1_1") (pintype "passive"))
      (node (ref "C16") (pin "1") (pinfunction "1_1") (pintype "passive"))
      (node (ref "C17") (pin "1") (pinfunction "1_1") (pintype "passive"))
      (node (ref "C4") (pin "2") (pinfunction "2_2") (pintype "passive"))
      (node (ref "L1") (pin "1") (pinfunction "1_1") (pintype "passive"))
      (node (ref "Q2") (pin "1") (pinfunction "G_1") (pintype "passive"))
      (node (ref "Q3") (pin "1") (pinfunction "G_1") (pintype "passive"))
      (node (ref "R1") (pin "2") (pinfunction "2_2") (pintype "passive"))
      (node (ref "R12") (pin "2") (pinfunction "2_2") (pintype "passive"))
      (node (ref "R13") (pin "2") (pinfunction "2_2") (pintype "passive"))
      (node (ref "R14") (pin "2") (pinfunction "2_2") (pintype "passive"))
      (node (ref "R2") (pin "2") (pinfunction "2_2") (pintype "passive"))
      (node (ref "U1") (pin "4") (pinfunction "NC_4") (pintype "input"))
      (node (ref "U1") (pin "5") (pinfunction "OUT_5") (pintype "passive"))
      (node (ref "U2") (pin "24") (pinfunction "VDDIO_24") (pintype "bidirectional"))
      (node (ref "U2") (pin "30") (pinfunction "VDDIN_30") (pintype "bidirectional"))
      (node (ref "U9") (pin "VCC") (pinfunction "VCC_VCC") (pintype "bidirectional"))
    )
    (net (code "38") (name "GND") (class "Default")
      (node (ref "C1") (pin "2") (pinfunction "2_2") (pintype "passive"))
      (node (ref "C10") (pin "1") (pinfunction "1_1") (pintype "passive"))
      (node (ref "C11") (pin "2") (pinfunction "2_2") (pintype "passive"))
      (node (ref "C12") (pin "2") (pinfunction "2_2") (pintype "passive"))
      (node (ref "C13") (pin "2") (pinfunction "2_2") (pintype "passive"))
      (node (ref "C14") (pin "2") (pinfunction "2_2") (pintype "passive"))
      (node (ref "C15") (pin "2") (pinfunction "2_2") (pintype "passive"))
      (node (ref "C16") (pin "2") (pinfunction "2_2") (pintype "passive"))
      (node (ref "C17") (pin "2") (pinfunction "2_2") (pintype "passive"))
      (node (ref "C18") (pin "2") (pinfunction "2_2") (pintype "passive"))
      (node (ref "C19") (pin "2") (pinfunction "2_2") (pintype "passive"))
      (node (ref "C2") (pin "1") (pinfunction "1_1") (pintype "passive"))
      (node (ref "C20") (pin "2") (pinfunction "2_2") (pintype "passive"))
      (node (ref "C21") (pin "2") (pinfunction "2_2") (pintype "passive"))
      (node (ref "C22") (pin "2") (pinfunction "2_2") (pintype "passive"))
      (node (ref "C3") (pin "1") (pinfunction "1_1") (pintype "passive"))
      (node (ref "C4") (pin "1") (pinfunction "1_1") (pintype "passive"))
      (node (ref "C7") (pin "2") (pinfunction "2_2") (pintype "passive"))
      (node (ref "C8") (pin "2") (pinfunction "2_2") (pintype "passive"))
      (node (ref "C9") (pin "2") (pinfunction "2_2") (pintype "passive"))
      (node (ref "D1") (pin "C") (pinfunction "C_C") (pintype "passive"))
      (node (ref "Q1") (pin "2") (pinfunction "S_2") (pintype "passive"))
      (node (ref "R4") (pin "1") (pinfunction "1_1") (pintype "passive"))
      (node (ref "R7") (pin "1") (pinfunction "1_1") (pintype "passive"))
      (node (ref "S2") (pin "1") (pinfunction "1_1") (pintype "passive"))
      (node (ref "S2") (pin "2") (pinfunction "1_2") (pintype "passive"))
      (node (ref "U1") (pin "2") (pinfunction "GND_2") (pintype "input"))
      (node (ref "U10") (pin "8") (pinfunction "GND_8") (pintype "bidirectional"))
      (node (ref "U11") (pin "P$4") (pinfunction "P$1_P$4") (pintype "bidirectional"))
      (node (ref "U11") (pin "P$5") (pinfunction "P$5_P$5") (pintype "bidirectional"))
      (node (ref "U11") (pin "P$6") (pinfunction "P$6_P$6") (pintype "bidirectional"))
      (node (ref "U12") (pin "P$4") (pinfunction "P$1_P$4") (pintype "bidirectional"))
      (node (ref "U12") (pin "P$5") (pinfunction "P$5_P$5") (pintype "bidirectional"))
      (node (ref "U12") (pin "P$6") (pinfunction "P$6_P$6") (pintype "bidirectional"))
      (node (ref "U13") (pin "P$4") (pinfunction "P$1_P$4") (pintype "bidirectional"))
      (node (ref "U13") (pin "P$5") (pinfunction "P$5_P$5") (pintype "bidirectional"))
      (node (ref "U13") (pin "P$6") (pinfunction "P$6_P$6") (pintype "bidirectional"))
      (node (ref "U16") (pin "P$1") (pinfunction "P$4_P$1") (pintype "bidirectional"))
      (node (ref "U16") (pin "P$5") (pinfunction "P$5_P$5") (pintype "bidirectional"))
      (node (ref "U16") (pin "P$6") (pinfunction "P$6_P$6") (pintype "bidirectional"))
      (node (ref "U18") (pin "10") (pinfunction "P$10_10") (pintype "bidirectional"))
      (node (ref "U18") (pin "4") (pinfunction "P$4_4") (pintype "bidirectional"))
      (node (ref "U18") (pin "5") (pinfunction "P$5_5") (pintype "bidirectional"))
      (node (ref "U18") (pin "6") (pinfunction "P$6_6") (pintype "bidirectional"))
      (node (ref "U18") (pin "7") (pinfunction "P$7_7") (pintype "bidirectional"))
      (node (ref "U18") (pin "8") (pinfunction "P$8_8") (pintype "bidirectional"))
      (node (ref "U18") (pin "9") (pinfunction "P$9_9") (pintype "bidirectional"))
      (node (ref "U2") (pin "11") (pinfunction "GNDANA_11") (pintype "bidirectional"))
      (node (ref "U2") (pin "14") (pinfunction "GNDANA_14") (pintype "bidirectional"))
      (node (ref "U2") (pin "3") (pinfunction "GNDANA_3") (pintype "bidirectional"))
      (node (ref "U2") (pin "33") (pinfunction "GND_PAD_33") (pintype "bidirectional"))
      (node (ref "U2") (pin "6") (pinfunction "GNDANA_6") (pintype "bidirectional"))
      (node (ref "U21") (pin "GND") (pinfunction "GND_GND") (pintype "bidirectional"))
      (node (ref "U5") (pin "3") (pinfunction "3_3") (pintype "bidirectional"))
      (node (ref "U6") (pin "2") (pinfunction "2_2") (pintype "bidirectional"))
      (node (ref "U6") (pin "5") (pinfunction "5_5") (pintype "bidirectional"))
      (node (ref "U6") (pin "6") (pinfunction "6_6") (pintype "bidirectional"))
      (node (ref "U7") (pin "2") (pinfunction "GND_2") (pintype "bidirectional"))
      (node (ref "U7") (pin "4") (pinfunction "GND_4") (pintype "bidirectional"))
      (node (ref "U8") (pin "5") (pinfunction "GND_5") (pintype "power_in"))
      (node (ref "U9") (pin "GND") (pinfunction "GND_GND") (pintype "bidirectional"))
      (node (ref "Y1") (pin "2") (pinfunction "2_2") (pintype "passive"))
    )
    (net (code "39") (name "Net-(C5-Pad2)") (class "Default")
      (node (ref "C5") (pin "2") (pinfunction "2_2") (pintype "passive"))
      (node (ref "U6") (pin "3") (pinfunction "3_3") (pintype "bidirectional"))
    )
    (net (code "40") (name "Net-(C6-Pad1)") (class "Default")
      (node (ref "C6") (pin "1") (pinfunction "1_1") (pintype "passive"))
      (node (ref "U6") (pin "4") (pinfunction "4_4") (pintype "bidirectional"))
    )
    (net (code "41") (name "Net-(C7-Pad1)") (class "Default")
      (node (ref "C7") (pin "1") (pinfunction "1_1") (pintype "passive"))
      (node (ref "U5") (pin "2") (pinfunction "2_2") (pintype "bidirectional"))
    )
    (net (code "42") (name "Net-(C9-Pad1)") (class "Default")
      (node (ref "C9") (pin "1") (pinfunction "1_1") (pintype "passive"))
      (node (ref "R5") (pin "1") (pinfunction "1_1") (pintype "passive"))
    )
    (net (code "43") (name "Net-(D1-PadA)") (class "Default")
      (node (ref "D1") (pin "A") (pinfunction "A_A") (pintype "passive"))
      (node (ref "R1") (pin "1") (pinfunction "1_1") (pintype "passive"))
    )
    (net (code "44") (name "Net-(D2-PadC)") (class "Default")
      (node (ref "D2") (pin "C") (pinfunction "C_C") (pintype "passive"))
      (node (ref "R20") (pin "2") (pinfunction "2_2") (pintype "passive"))
    )
    (net (code "45") (name "Net-(D5-PadA)") (class "Default")
      (node (ref "D5") (pin "A") (pinfunction "A_A") (pintype "passive"))
      (node (ref "R12") (pin "1") (pinfunction "1_1") (pintype "passive"))
    )
    (net (code "46") (name "Net-(F2-Pad1)") (class "Default")
      (node (ref "F2") (pin "1") (pinfunction "1_1") (pintype "bidirectional"))
      (node (ref "U17") (pin "8") (pinfunction "8_8") (pintype "bidirectional"))
    )
    (net (code "47") (name "Net-(F3-Pad1)") (class "Default")
      (node (ref "F3") (pin "1") (pinfunction "1_1") (pintype "bidirectional"))
      (node (ref "U17") (pin "5") (pinfunction "5_5") (pintype "bidirectional"))
    )
    (net (code "48") (name "Net-(F4-Pad1)") (class "Default")
      (node (ref "F4") (pin "1") (pinfunction "1_1") (pintype "bidirectional"))
      (node (ref "U17") (pin "2") (pinfunction "2_2") (pintype "bidirectional"))
    )
    (net (code "49") (name "Net-(J1-VCC)") (class "Default")
      (node (ref "J1") (pin "VBUS") (pinfunction "VCC_VBUS") (pintype "bidirectional"))
      (node (ref "U14") (pin "P$4") (pinfunction "P$1_P$4") (pintype "bidirectional"))
    )
    (net (code "50") (name "Net-(Q1-D)") (class "Default")
      (node (ref "D5") (pin "C") (pinfunction "C_C") (pintype "passive"))
      (node (ref "Q1") (pin "3") (pinfunction "D_3") (pintype "passive"))
    )
    (net (code "51") (name "Net-(Q4-G)") (class "Default")
      (node (ref "Q4") (pin "4") (pinfunction "G_4") (pintype "passive"))
      (node (ref "R19") (pin "1") (pinfunction "1_1") (pintype "passive"))
      (node (ref "S1") (pin "2") (pinfunction "2_2") (pintype "bidirectional"))
    )
    (net (code "52") (name "Net-(R3-Pad2)") (class "Default")
      (node (ref "R3") (pin "2") (pinfunction "2_2") (pintype "passive"))
      (node (ref "S2") (pin "3") (pinfunction "2_3") (pintype "passive"))
      (node (ref "S2") (pin "4") (pinfunction "2_4") (pintype "passive"))
    )
    (net (code "53") (name "Net-(R18-2)") (class "Default")
      (node (ref "Q4") (pin "1") (pinfunction "S_1") (pintype "passive"))
      (node (ref "Q4") (pin "2") (pinfunction "S_2") (pintype "passive"))
      (node (ref "Q4") (pin "3") (pinfunction "S_3") (pintype "passive"))
      (node (ref "R18") (pin "P$2") (pinfunction "2_P$2") (pintype "passive"))
      (node (ref "R19") (pin "2") (pinfunction "2_2") (pintype "passive"))
      (node (ref "S1") (pin "1") (pinfunction "1_1") (pintype "bidirectional"))
    )
    (net (code "54") (name "Net-(U5-Pad1)") (class "Default")
      (node (ref "U5") (pin "1") (pinfunction "1_1") (pintype "bidirectional"))
      (node (ref "U6") (pin "1") (pinfunction "1_1") (pintype "bidirectional"))
    )
    (net (code "55") (name "Net-(U8-BOOT)") (class "Default")
      (node (ref "C25") (pin "1") (pinfunction "1_1") (pintype "passive"))
      (node (ref "U8") (pin "10") (pinfunction "BOOT_10") (pintype "power_in"))
    )
    (net (code "56") (name "Net-(U8-COMP)") (class "Default")
      (node (ref "C18") (pin "1") (pinfunction "1_1") (pintype "passive"))
      (node (ref "R5") (pin "2") (pinfunction "2_2") (pintype "passive"))
      (node (ref "U8") (pin "4") (pinfunction "COMP_4") (pintype "output"))
    )
    (net (code "57") (name "Net-(U8-EN)") (class "Default")
      (node (ref "C21") (pin "1") (pinfunction "1_1") (pintype "passive"))
      (node (ref "U8") (pin "2") (pinfunction "VCC_2") (pintype "power_in"))
      (node (ref "U8") (pin "7") (pinfunction "EN_7") (pintype "input"))
    )
    (net (code "58") (name "Net-(U8-FB)") (class "Default")
      (node (ref "R6") (pin "1") (pinfunction "1_1") (pintype "passive"))
      (node (ref "R7") (pin "2") (pinfunction "2_2") (pintype "passive"))
      (node (ref "U8") (pin "3") (pinfunction "FB_3") (pintype "input"))
    )
    (net (code "59") (name "Net-(U8-FSW)") (class "Default")
      (node (ref "R10") (pin "2") (pinfunction "2_2") (pintype "passive"))
      (node (ref "U8") (pin "1") (pinfunction "FSW_1") (pintype "input"))
    )
    (net (code "60") (name "Net-(U8-ILIM)") (class "Default")
      (node (ref "R4") (pin "2") (pinfunction "2_2") (pintype "passive"))
      (node (ref "U8") (pin "8") (pinfunction "ILIM_8") (pintype "input"))
    )
    (net (code "61") (name "Net-(U8-SW)") (class "Default")
      (node (ref "C25") (pin "2") (pinfunction "2_2") (pintype "passive"))
      (node (ref "L2") (pin "P$2") (pinfunction "P$2_P$2") (pintype "bidirectional"))
      (node (ref "R10") (pin "1") (pinfunction "1_1") (pintype "passive"))
      (node (ref "U8") (pin "11") (pinfunction "SW_11") (pintype "power_in"))
    )
    (net (code "62") (name "Net-(U10-(PCINT8{slash}XTAL1{slash}CLKI)PB0)") (class "Default")
      (node (ref "U10") (pin "11") (pinfunction "(PCINT8/XTAL1/CLKI)PB0_11") (pintype "bidirectional"))
      (node (ref "Y1") (pin "1") (pinfunction "1_1") (pintype "passive"))
    )
    (net (code "63") (name "Net-(U10-(PCINT9{slash}XTAL2)PB1)") (class "Default")
      (node (ref "U10") (pin "12") (pinfunction "(PCINT9/XTAL2)PB1_12") (pintype "bidirectional"))
      (node (ref "Y1") (pin "3") (pinfunction "3_3") (pintype "passive"))
    )
    (net (code "64") (name "Net-(U14-P$2)") (class "Default")
      (node (ref "J1") (pin "D-") (pinfunction "D-_D-") (pintype "bidirectional"))
      (node (ref "U14") (pin "P$3") (pinfunction "P$2_P$3") (pintype "bidirectional"))
    )
    (net (code "65") (name "Net-(U14-P$3)") (class "Default")
      (node (ref "J1") (pin "D+") (pinfunction "D+_D+") (pintype "bidirectional"))
      (node (ref "U14") (pin "P$2") (pinfunction "P$3_P$2") (pintype "bidirectional"))
    )
    (net (code "66") (name "Net-(U14-P$4)") (class "Default")
      (node (ref "J1") (pin "GND") (pinfunction "GND_GND") (pintype "bidirectional"))
      (node (ref "J1") (pin "SHIELD1") (pinfunction "SHIELD_SHIELD1") (pintype "bidirectional"))
      (node (ref "J1") (pin "SHIELD2") (pinfunction "SHIELD_SHIELD2") (pintype "bidirectional"))
      (node (ref "J1") (pin "SHIELD3") (pinfunction "SHIELD_SHIELD3") (pintype "bidirectional"))
      (node (ref "U14") (pin "P$1") (pinfunction "P$4_P$1") (pintype "bidirectional"))
      (node (ref "U14") (pin "P$5") (pinfunction "P$5_P$5") (pintype "bidirectional"))
      (node (ref "U14") (pin "P$6") (pinfunction "P$6_P$6") (pintype "bidirectional"))
    )
    (net (code "67") (name "Net-(U20-A0)") (class "Default")
      (node (ref "JP1") (pin "1") (pinfunction "1_1") (pintype "passive"))
      (node (ref "R16") (pin "2") (pinfunction "2_2") (pintype "passive"))
      (node (ref "U20") (pin "7") (pinfunction "A0_7") (pintype "bidirectional"))
    )
    (net (code "68") (name "Net-(U20-A1)") (class "Default")
      (node (ref "JP2") (pin "1") (pinfunction "1_1") (pintype "passive"))
      (node (ref "R17") (pin "2") (pinfunction "2_2") (pintype "passive"))
      (node (ref "U20") (pin "8") (pinfunction "A1_8") (pintype "bidirectional"))
    )
    (net (code "69") (name "VIN") (class "Default")
      (node (ref "C3") (pin "2") (pinfunction "2_2") (pintype "passive"))
      (node (ref "F1") (pin "2") (pinfunction "2_2") (pintype "bidirectional"))
      (node (ref "U1") (pin "1") (pinfunction "IN_1") (pintype "input"))
      (node (ref "U1") (pin "3") (pinfunction "EN_3") (pintype "input"))
    )
    (net (code "70") (name "unconnected-(J1-PadID)") (class "Default")
      (node (ref "J1") (pin "ID") (pinfunction "ID_ID") (pintype "bidirectional"))
    )
    (net (code "71") (name "unconnected-(U2-GND-Pad28)") (class "Default")
      (node (ref "U2") (pin "28") (pinfunction "GND_28") (pintype "bidirectional"))
    )
    (net (code "72") (name "unconnected-(U2-PA06-Pad7)") (class "Default")
      (node (ref "U2") (pin "7") (pinfunction "PA06_7") (pintype "bidirectional"))
    )
    (net (code "73") (name "unconnected-(U2-PA07-Pad8)") (class "Default")
      (node (ref "U2") (pin "8") (pinfunction "PA07_8") (pintype "bidirectional"))
    )
    (net (code "74") (name "unconnected-(U2-PA14-Pad15)") (class "Default")
      (node (ref "U2") (pin "15") (pinfunction "PA14_15") (pintype "bidirectional"))
    )
    (net (code "75") (name "unconnected-(U2-PA15-Pad16)") (class "Default")
      (node (ref "U2") (pin "16") (pinfunction "PA15_16") (pintype "bidirectional"))
    )
    (net (code "76") (name "unconnected-(U2-PA16-Pad17)") (class "Default")
      (node (ref "U2") (pin "17") (pinfunction "PA16_17") (pintype "bidirectional"))
    )
    (net (code "77") (name "unconnected-(U2-PA18-Pad19)") (class "Default")
      (node (ref "U2") (pin "19") (pinfunction "PA18_19") (pintype "bidirectional"))
    )
    (net (code "78") (name "unconnected-(U2-PA19-Pad20)") (class "Default")
      (node (ref "U2") (pin "20") (pinfunction "PA19_20") (pintype "bidirectional"))
    )
    (net (code "79") (name "unconnected-(U2-PA27-Pad25)") (class "Default")
      (node (ref "U2") (pin "25") (pinfunction "PA27_25") (pintype "bidirectional"))
    )
    (net (code "80") (name "unconnected-(U2-PA28-Pad27)") (class "Default")
      (node (ref "U2") (pin "27") (pinfunction "PA28_27") (pintype "bidirectional"))
    )
    (net (code "81") (name "unconnected-(U9-PadMOSI)") (class "Default")
      (node (ref "U9") (pin "MOSI") (pinfunction "MOSI_MOSI") (pintype "bidirectional"))
    )
    (net (code "82") (name "unconnected-(U10-(PCINT0{slash}AREF{slash}ADC0)PA0-Pad5)") (class "Default")
      (node (ref "U10") (pin "5") (pinfunction "(PCINT0/AREF/ADC0)PA0_5") (pintype "bidirectional"))
    )
    (net (code "83") (name "unconnected-(U10-(PCINT2{slash}AIN1{slash}ADC2)PA2-Pad3)") (class "Default")
      (node (ref "U10") (pin "3") (pinfunction "(PCINT2/AIN1/ADC2)PA2_3") (pintype "bidirectional"))
    )
    (net (code "84") (name "unconnected-(U10-(PCINT3{slash}T0{slash}ADC3)PA3-Pad2)") (class "Default")
      (node (ref "U10") (pin "2") (pinfunction "(PCINT3/T0/ADC3)PA3_2") (pintype "bidirectional"))
    )
  )
)
